# I3C_and_I2C_Slaves.net
KiCad netlist of a schematic drawn in Altium Designer
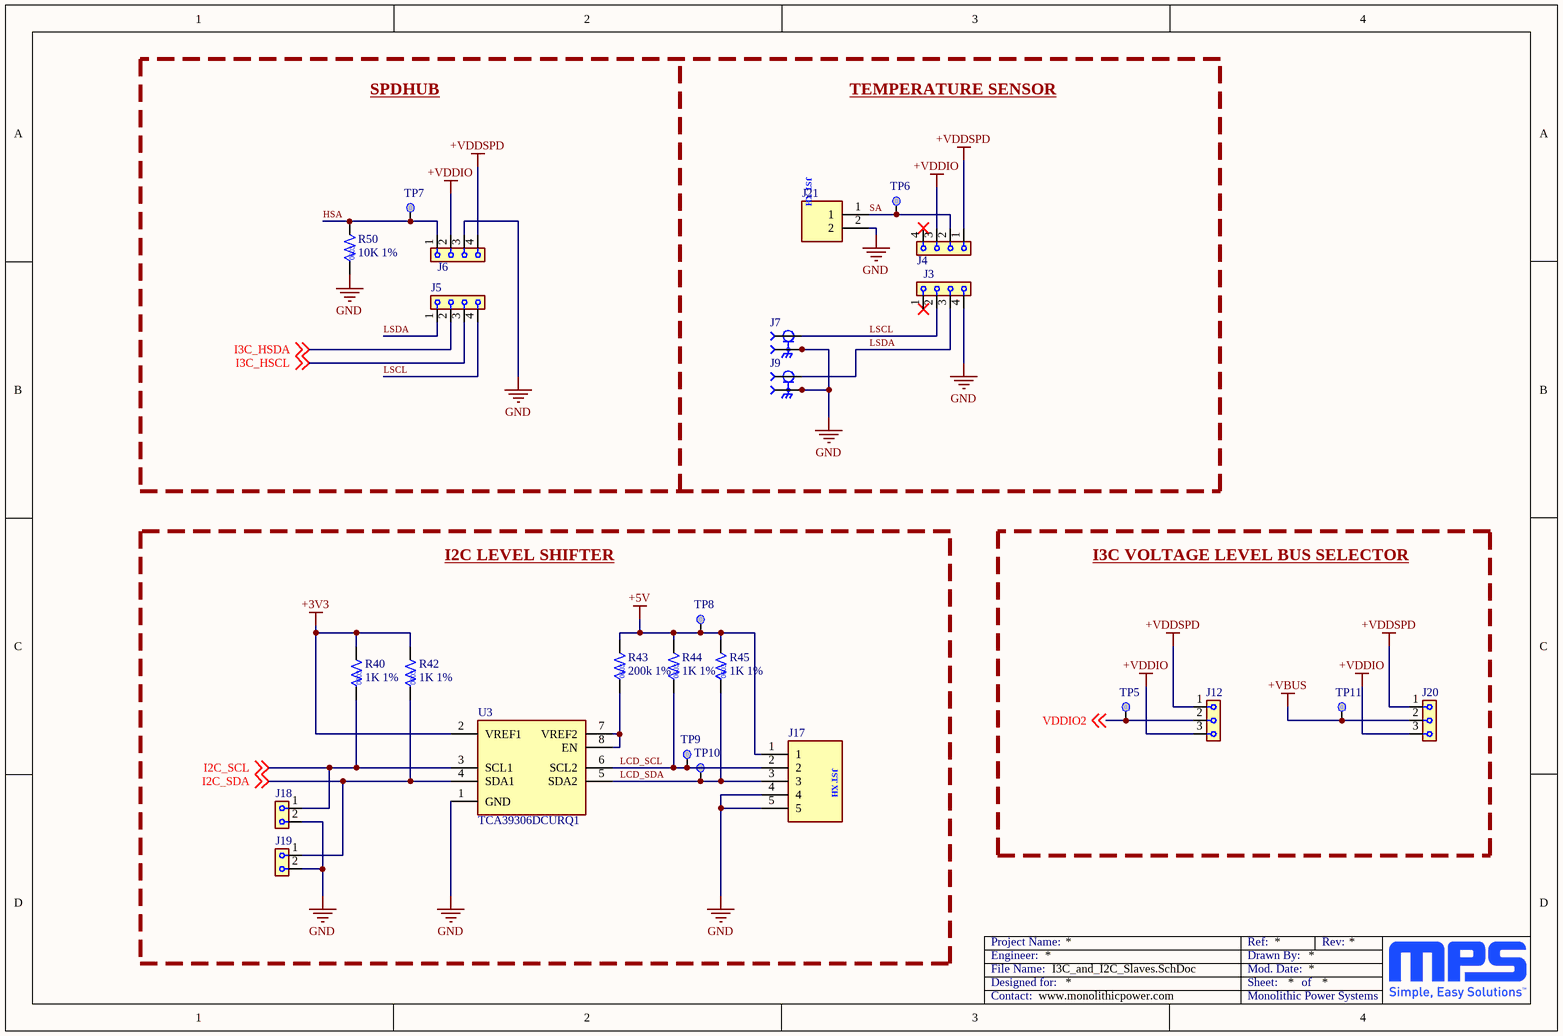
[diagram p0: I3C_and_I2C_Slaves.SchDoc]

(export (version "E")
  (design (tool "Eeschema 10.0.6"))
  (components
    (comp (ref "J3")
      (value "61300411821")
      (footprint "61300411821")
      (description "2.54mm Scket Header 4 pins")
      (fields (field (name "MANUFACTURER") "Wurth Elektronik"))
      (libsource (lib "DDR5_Nucleo_Shield_Symbols") (part "61300411821"))
    )
    (comp (ref "J4")
      (value "61300411821")
      (footprint "61300411821")
      (description "2.54mm Scket Header 4 pins")
      (fields (field (name "MANUFACTURER") "Wurth Elektronik"))
      (libsource (lib "") (part "61300411821_1"))
    )
    (comp (ref "J5")
      (value "61300411821")
      (footprint "61300411821")
      (description "2.54mm Scket Header 4 pins")
      (fields (field (name "MANUFACTURER") "Wurth Elektronik"))
      (libsource (lib "DDR5_Nucleo_Shield_Symbols") (part "61300411821"))
    )
    (comp (ref "J6")
      (value "61300411821")
      (footprint "61300411821")
      (description "2.54mm Scket Header 4 pins")
      (fields (field (name "MANUFACTURER") "Wurth Elektronik"))
      (libsource (lib "") (part "61300411821_2"))
    )
    (comp (ref "J7")
      (value "MMCX-J-P-H-ST-TH1")
      (footprint "SAMTEC_MMCX-J-P-H-ST-TH1")
      (description "RF Connectors / Coaxial Connectors 50 OHM MMCX JACK OR PLUG")
      (fields (field (name "MANUFACTURER") "Samtec Inc."))
      (libsource (lib "DDR5_Nucleo_Shield_Symbols") (part "MMCX-J-P-H-ST-TH1"))
    )
    (comp (ref "J9")
      (value "MMCX-J-P-H-ST-TH1")
      (footprint "SAMTEC_MMCX-J-P-H-ST-TH1")
      (description "RF Connectors / Coaxial Connectors 50 OHM MMCX JACK OR PLUG")
      (fields (field (name "MANUFACTURER") "Samtec Inc."))
      (libsource (lib "DDR5_Nucleo_Shield_Symbols") (part "MMCX-J-P-H-ST-TH1"))
    )
    (comp (ref "J12")
      (value "TSW-103-07-F-S")
      (footprint "HEADER/VERT/1X3/M/P2.54")
      (description "Pin Header, Unshrouded, Board-to-Board, 2.54 mm, 1 Rows, 3 Contacts, Through Hole, TSW")
      (fields (field (name "MANUFACTURER") "SAMTEC"))
      (libsource (lib "DDR5_Nucleo_Shield_Symbols") (part "TSW-103-07-F-S"))
    )
    (comp (ref "J17")
      (value "B5B-XH-A(LF)(SN)")
      (footprint "JST_XH_5V")
      (description "Alojamientos de cables y cabecera XH HEADER (TOP)")
      (fields (field (name "MANUFACTURER") "JST"))
      (libsource (lib "DDR5_Nucleo_Shield_Symbols") (part "B5B-XH-A(LF)(SN)"))
    )
    (comp (ref "J18")
      (value "TSW-102-07-F-S")
      (footprint "HEADER/VERT/1X2/M/P2.54")
      (description "Alojamientos de cables y cabecera 2.54MM CLASSIC PCB HDR STRIP")
      (fields (field (name "MANUFACTURER") "SAMTEC"))
      (libsource (lib "DDR5_Nucleo_Shield_Symbols") (part "TSW-102-07-F-S"))
    )
    (comp (ref "J19")
      (value "TSW-102-07-F-S")
      (footprint "HEADER/VERT/1X2/M/P2.54")
      (description "Alojamientos de cables y cabecera 2.54MM CLASSIC PCB HDR STRIP")
      (fields (field (name "MANUFACTURER") "SAMTEC"))
      (libsource (lib "DDR5_Nucleo_Shield_Symbols") (part "TSW-102-07-F-S"))
    )
    (comp (ref "J20")
      (value "TSW-103-07-F-S")
      (footprint "HEADER/VERT/1X3/M/P2.54")
      (description "Pin Header, Unshrouded, Board-to-Board, 2.54 mm, 1 Rows, 3 Contacts, Through Hole, TSW")
      (fields (field (name "MANUFACTURER") "SAMTEC"))
      (libsource (lib "DDR5_Nucleo_Shield_Symbols") (part "TSW-103-07-F-S"))
    )
    (comp (ref "J21")
      (value "B2B-XH-A (LF)(SN)")
      (footprint "JST_XH_2V")
      (description "Alojamientos de cables y cabecera 2.54MM CLASSIC PCB HDR STRIP")
      (fields (field (name "MANUFACTURER") "JST"))
      (libsource (lib "DDR5_Nucleo_Shield_Symbols") (part "B2B-XH-A (LF)(SN)"))
    )
    (comp (ref "R40")
      (value "1K 1%")
      (footprint "CC/NM 0603")
      (fields
        (field (name "MANUFACTURER") "YAGEO")
        (field (name "MANUFACTURER PART NUMBER") "RT0603BRD101KL")
      )
      (libsource (lib "DDR5_Nucleo_Shield_Symbols") (part "RT0603BRD101KL"))
    )
    (comp (ref "R42")
      (value "1K 1%")
      (footprint "CC/NM 0603")
      (fields
        (field (name "MANUFACTURER") "YAGEO")
        (field (name "MANUFACTURER PART NUMBER") "RT0603BRD101KL")
      )
      (libsource (lib "DDR5_Nucleo_Shield_Symbols") (part "RT0603BRD101KL"))
    )
    (comp (ref "R43")
      (value "200k 1%")
      (footprint "CC/NM 0603")
      (description "Resistores de película gruesa - SMD D11/CRCW0603-P 50 200K 1% ET1 e3")
      (fields (field (name "MANUFACTURER PART NUMBER") "CRCW0603200KFHEAP"))
      (libsource (lib "DDR5_Nucleo_Shield_Symbols") (part "CRCW0603200KFHEAP"))
    )
    (comp (ref "R44")
      (value "1K 1%")
      (footprint "CC/NM 0603")
      (fields
        (field (name "MANUFACTURER") "YAGEO")
        (field (name "MANUFACTURER PART NUMBER") "RT0603BRD101KL")
      )
      (libsource (lib "DDR5_Nucleo_Shield_Symbols") (part "RT0603BRD101KL"))
    )
    (comp (ref "R45")
      (value "1K 1%")
      (footprint "CC/NM 0603")
      (fields
        (field (name "MANUFACTURER") "YAGEO")
        (field (name "MANUFACTURER PART NUMBER") "RT0603BRD101KL")
      )
      (libsource (lib "DDR5_Nucleo_Shield_Symbols") (part "RT0603BRD101KL"))
    )
    (comp (ref "R50")
      (value "10K 1%")
      (footprint "CC/NM 0603")
      (fields
        (field (name "MANUFACTURER") "YAGEO")
        (field (name "MANUFACTURER PART NUMBER") "AC0603FR-0710KL")
      )
      (libsource (lib "DDR5_Nucleo_Shield_Symbols") (part "AC0603FR-0710KL"))
    )
    (comp (ref "TP5")
      (value "Test Point")
      (footprint "TP_SMD_1MM")
      (description "Test Point 1mm")
      (fields
        (field (name "INTERNAL_PART_NUMBER") "MCD-00074")
        (field (name "MANUFACTURER_PART_NUMBER") "n/a")
      )
      (libsource (lib "DDR5_Nucleo_Shield_Symbols") (part "Test_Point_1mm"))
    )
    (comp (ref "TP6")
      (value "Test Point")
      (footprint "TP_SMD_1MM")
      (description "Test Point 1mm")
      (fields
        (field (name "INTERNAL_PART_NUMBER") "MCD-00074")
        (field (name "MANUFACTURER_PART_NUMBER") "n/a")
      )
      (libsource (lib "DDR5_Nucleo_Shield_Symbols") (part "Test_Point_1mm"))
    )
    (comp (ref "TP7")
      (value "Test Point")
      (footprint "TP_SMD_1MM")
      (description "Test Point 1mm")
      (fields
        (field (name "INTERNAL_PART_NUMBER") "MCD-00074")
        (field (name "MANUFACTURER_PART_NUMBER") "n/a")
      )
      (libsource (lib "DDR5_Nucleo_Shield_Symbols") (part "Test_Point_1mm"))
    )
    (comp (ref "TP8")
      (value "Test Point")
      (footprint "TP_SMD_1MM")
      (description "Test Point 1mm")
      (fields
        (field (name "INTERNAL_PART_NUMBER") "MCD-00074")
        (field (name "MANUFACTURER_PART_NUMBER") "n/a")
      )
      (libsource (lib "DDR5_Nucleo_Shield_Symbols") (part "Test_Point_1mm"))
    )
    (comp (ref "TP9")
      (value "Test Point")
      (footprint "TP_SMD_1MM")
      (description "Test Point 1mm")
      (fields
        (field (name "INTERNAL_PART_NUMBER") "MCD-00074")
        (field (name "MANUFACTURER_PART_NUMBER") "n/a")
      )
      (libsource (lib "DDR5_Nucleo_Shield_Symbols") (part "Test_Point_1mm"))
    )
    (comp (ref "TP10")
      (value "Test Point")
      (footprint "TP_SMD_1MM")
      (description "Test Point 1mm")
      (fields
        (field (name "INTERNAL_PART_NUMBER") "MCD-00074")
        (field (name "MANUFACTURER_PART_NUMBER") "n/a")
      )
      (libsource (lib "DDR5_Nucleo_Shield_Symbols") (part "Test_Point_1mm"))
    )
    (comp (ref "TP11")
      (value "Test Point")
      (footprint "TP_SMD_1MM")
      (description "Test Point 1mm")
      (fields
        (field (name "INTERNAL_PART_NUMBER") "MCD-00074")
        (field (name "MANUFACTURER_PART_NUMBER") "n/a")
      )
      (libsource (lib "DDR5_Nucleo_Shield_Symbols") (part "Test_Point_1mm"))
    )
    (comp (ref "U3")
      (value "TCA39306DCURQ1")
      (footprint "SOP50P310X90-8N")
      (fields (field (name "MANUFACTURER") "TI"))
      (libsource (lib "altium-import") (part "root_0_TCA39306DCURQ1_"))
    )
  )
  (nets
    (net (code "1") (name "+3V3") (class "Default")
      (node (ref "R40") (pin "2") (pinfunction "2_2") (pintype "passive"))
      (node (ref "R42") (pin "2") (pinfunction "2_2") (pintype "passive"))
      (node (ref "U3") (pin "2") (pinfunction "VREF1_2") (pintype "passive"))
    )
    (net (code "2") (name "+5V") (class "Default")
      (node (ref "J17") (pin "1") (pinfunction "1_1") (pintype "passive"))
      (node (ref "R43") (pin "2") (pinfunction "2_2") (pintype "passive"))
      (node (ref "R44") (pin "2") (pinfunction "2_2") (pintype "passive"))
      (node (ref "R45") (pin "2") (pinfunction "2_2") (pintype "passive"))
      (node (ref "TP8") (pin "1") (pinfunction "1_1") (pintype "passive"))
    )
    (net (code "3") (name "+VBUS") (class "Default")
      (node (ref "J20") (pin "2") (pinfunction "2_2") (pintype "passive"))
      (node (ref "TP11") (pin "1") (pinfunction "1_1") (pintype "passive"))
    )
    (net (code "4") (name "+VDDIO") (class "Default")
      (node (ref "J12") (pin "3") (pinfunction "3_3") (pintype "passive"))
      (node (ref "J20") (pin "3") (pinfunction "3_3") (pintype "passive"))
      (node (ref "J4") (pin "3") (pinfunction "3_3") (pintype "passive"))
      (node (ref "J6") (pin "2") (pinfunction "2_2") (pintype "passive"))
    )
    (net (code "5") (name "+VDDSPD") (class "Default")
      (node (ref "J12") (pin "1") (pinfunction "1_1") (pintype "passive"))
      (node (ref "J20") (pin "1") (pinfunction "1_1") (pintype "passive"))
      (node (ref "J4") (pin "1") (pinfunction "1_1") (pintype "passive"))
      (node (ref "J6") (pin "4") (pinfunction "4_4") (pintype "passive"))
    )
    (net (code "6") (name "/HSA") (class "Default")
      (node (ref "J6") (pin "1") (pinfunction "1_1") (pintype "passive"))
      (node (ref "R50") (pin "2") (pinfunction "2_2") (pintype "passive"))
      (node (ref "TP7") (pin "1") (pinfunction "1_1") (pintype "passive"))
    )
    (net (code "7") (name "/LCD_SCL") (class "Default")
      (node (ref "J17") (pin "2") (pinfunction "2_2") (pintype "passive"))
      (node (ref "R44") (pin "1") (pinfunction "1_1") (pintype "passive"))
      (node (ref "TP9") (pin "1") (pinfunction "1_1") (pintype "passive"))
      (node (ref "U3") (pin "6") (pinfunction "SCL2_6") (pintype "passive"))
    )
    (net (code "8") (name "/LCD_SDA") (class "Default")
      (node (ref "J17") (pin "3") (pinfunction "3_3") (pintype "passive"))
      (node (ref "R45") (pin "1") (pinfunction "1_1") (pintype "passive"))
      (node (ref "TP10") (pin "1") (pinfunction "1_1") (pintype "passive"))
      (node (ref "U3") (pin "5") (pinfunction "SDA2_5") (pintype "passive"))
    )
    (net (code "9") (name "/LSCL") (class "Default")
      (node (ref "J3") (pin "2") (pinfunction "2_2") (pintype "passive"))
      (node (ref "J5") (pin "4") (pinfunction "4_4") (pintype "passive"))
      (node (ref "J7") (pin "1") (pinfunction "1_1") (pintype "passive"))
    )
    (net (code "10") (name "/LSDA") (class "Default")
      (node (ref "J3") (pin "3") (pinfunction "3_3") (pintype "passive"))
      (node (ref "J5") (pin "1") (pinfunction "1_1") (pintype "passive"))
      (node (ref "J9") (pin "1") (pinfunction "1_1") (pintype "passive"))
    )
    (net (code "11") (name "/SA") (class "Default")
      (node (ref "J21") (pin "1") (pinfunction "1_1") (pintype "passive"))
      (node (ref "J4") (pin "2") (pinfunction "2_2") (pintype "passive"))
      (node (ref "TP6") (pin "1") (pinfunction "1_1") (pintype "passive"))
    )
    (net (code "12") (name "GND") (class "Default")
      (node (ref "J17") (pin "4") (pinfunction "4_4") (pintype "passive"))
      (node (ref "J17") (pin "5") (pinfunction "5_5") (pintype "passive"))
      (node (ref "J18") (pin "2") (pinfunction "2_2") (pintype "passive"))
      (node (ref "J19") (pin "2") (pinfunction "2_2") (pintype "passive"))
      (node (ref "J21") (pin "2") (pinfunction "2_2") (pintype "passive"))
      (node (ref "J3") (pin "4") (pinfunction "4_4") (pintype "passive"))
      (node (ref "J6") (pin "3") (pinfunction "3_3") (pintype "passive"))
      (node (ref "J7") (pin "S1") (pinfunction "2_S1") (pintype "passive"))
      (node (ref "J7") (pin "S2") (pinfunction "2_S2") (pintype "passive"))
      (node (ref "J7") (pin "S3") (pinfunction "2_S3") (pintype "passive"))
      (node (ref "J7") (pin "S4") (pinfunction "2_S4") (pintype "passive"))
      (node (ref "J9") (pin "S1") (pinfunction "2_S1") (pintype "passive"))
      (node (ref "J9") (pin "S2") (pinfunction "2_S2") (pintype "passive"))
      (node (ref "J9") (pin "S3") (pinfunction "2_S3") (pintype "passive"))
      (node (ref "J9") (pin "S4") (pinfunction "2_S4") (pintype "passive"))
      (node (ref "R50") (pin "1") (pinfunction "1_1") (pintype "passive"))
      (node (ref "U3") (pin "1") (pinfunction "GND_1") (pintype "passive"))
    )
    (net (code "13") (name "I2C_SCL") (class "Default")
      (node (ref "J18") (pin "1") (pinfunction "1_1") (pintype "passive"))
      (node (ref "R40") (pin "1") (pinfunction "1_1") (pintype "passive"))
      (node (ref "U3") (pin "3") (pinfunction "SCL1_3") (pintype "passive"))
    )
    (net (code "14") (name "I2C_SDA") (class "Default")
      (node (ref "J19") (pin "1") (pinfunction "1_1") (pintype "passive"))
      (node (ref "R42") (pin "1") (pinfunction "1_1") (pintype "passive"))
      (node (ref "U3") (pin "4") (pinfunction "SDA1_4") (pintype "passive"))
    )
    (net (code "15") (name "I3C_HSCL") (class "Default")
      (node (ref "J5") (pin "3") (pinfunction "3_3") (pintype "passive"))
    )
    (net (code "16") (name "I3C_HSDA") (class "Default")
      (node (ref "J5") (pin "2") (pinfunction "2_2") (pintype "passive"))
    )
    (net (code "17") (name "Net-(U3-EN)") (class "Default")
      (node (ref "R43") (pin "1") (pinfunction "1_1") (pintype "passive"))
      (node (ref "U3") (pin "7") (pinfunction "VREF2_7") (pintype "passive"))
      (node (ref "U3") (pin "8") (pinfunction "EN_8") (pintype "passive"))
    )
    (net (code "18") (name "VDDIO2") (class "Default")
      (node (ref "J12") (pin "2") (pinfunction "2_2") (pintype "passive"))
      (node (ref "TP5") (pin "1") (pinfunction "1_1") (pintype "passive"))
    )
    (net (code "19") (name "unconnected-(J3-Pad1)") (class "Default")
      (node (ref "J3") (pin "1") (pinfunction "1_1") (pintype "passive+no_connect"))
    )
    (net (code "20") (name "unconnected-(J4-Pad4)") (class "Default")
      (node (ref "J4") (pin "4") (pinfunction "4_4") (pintype "passive+no_connect"))
    )
  )
)
